# Loginator.net
KiCad netlist of a schematic drawn in EAGLE
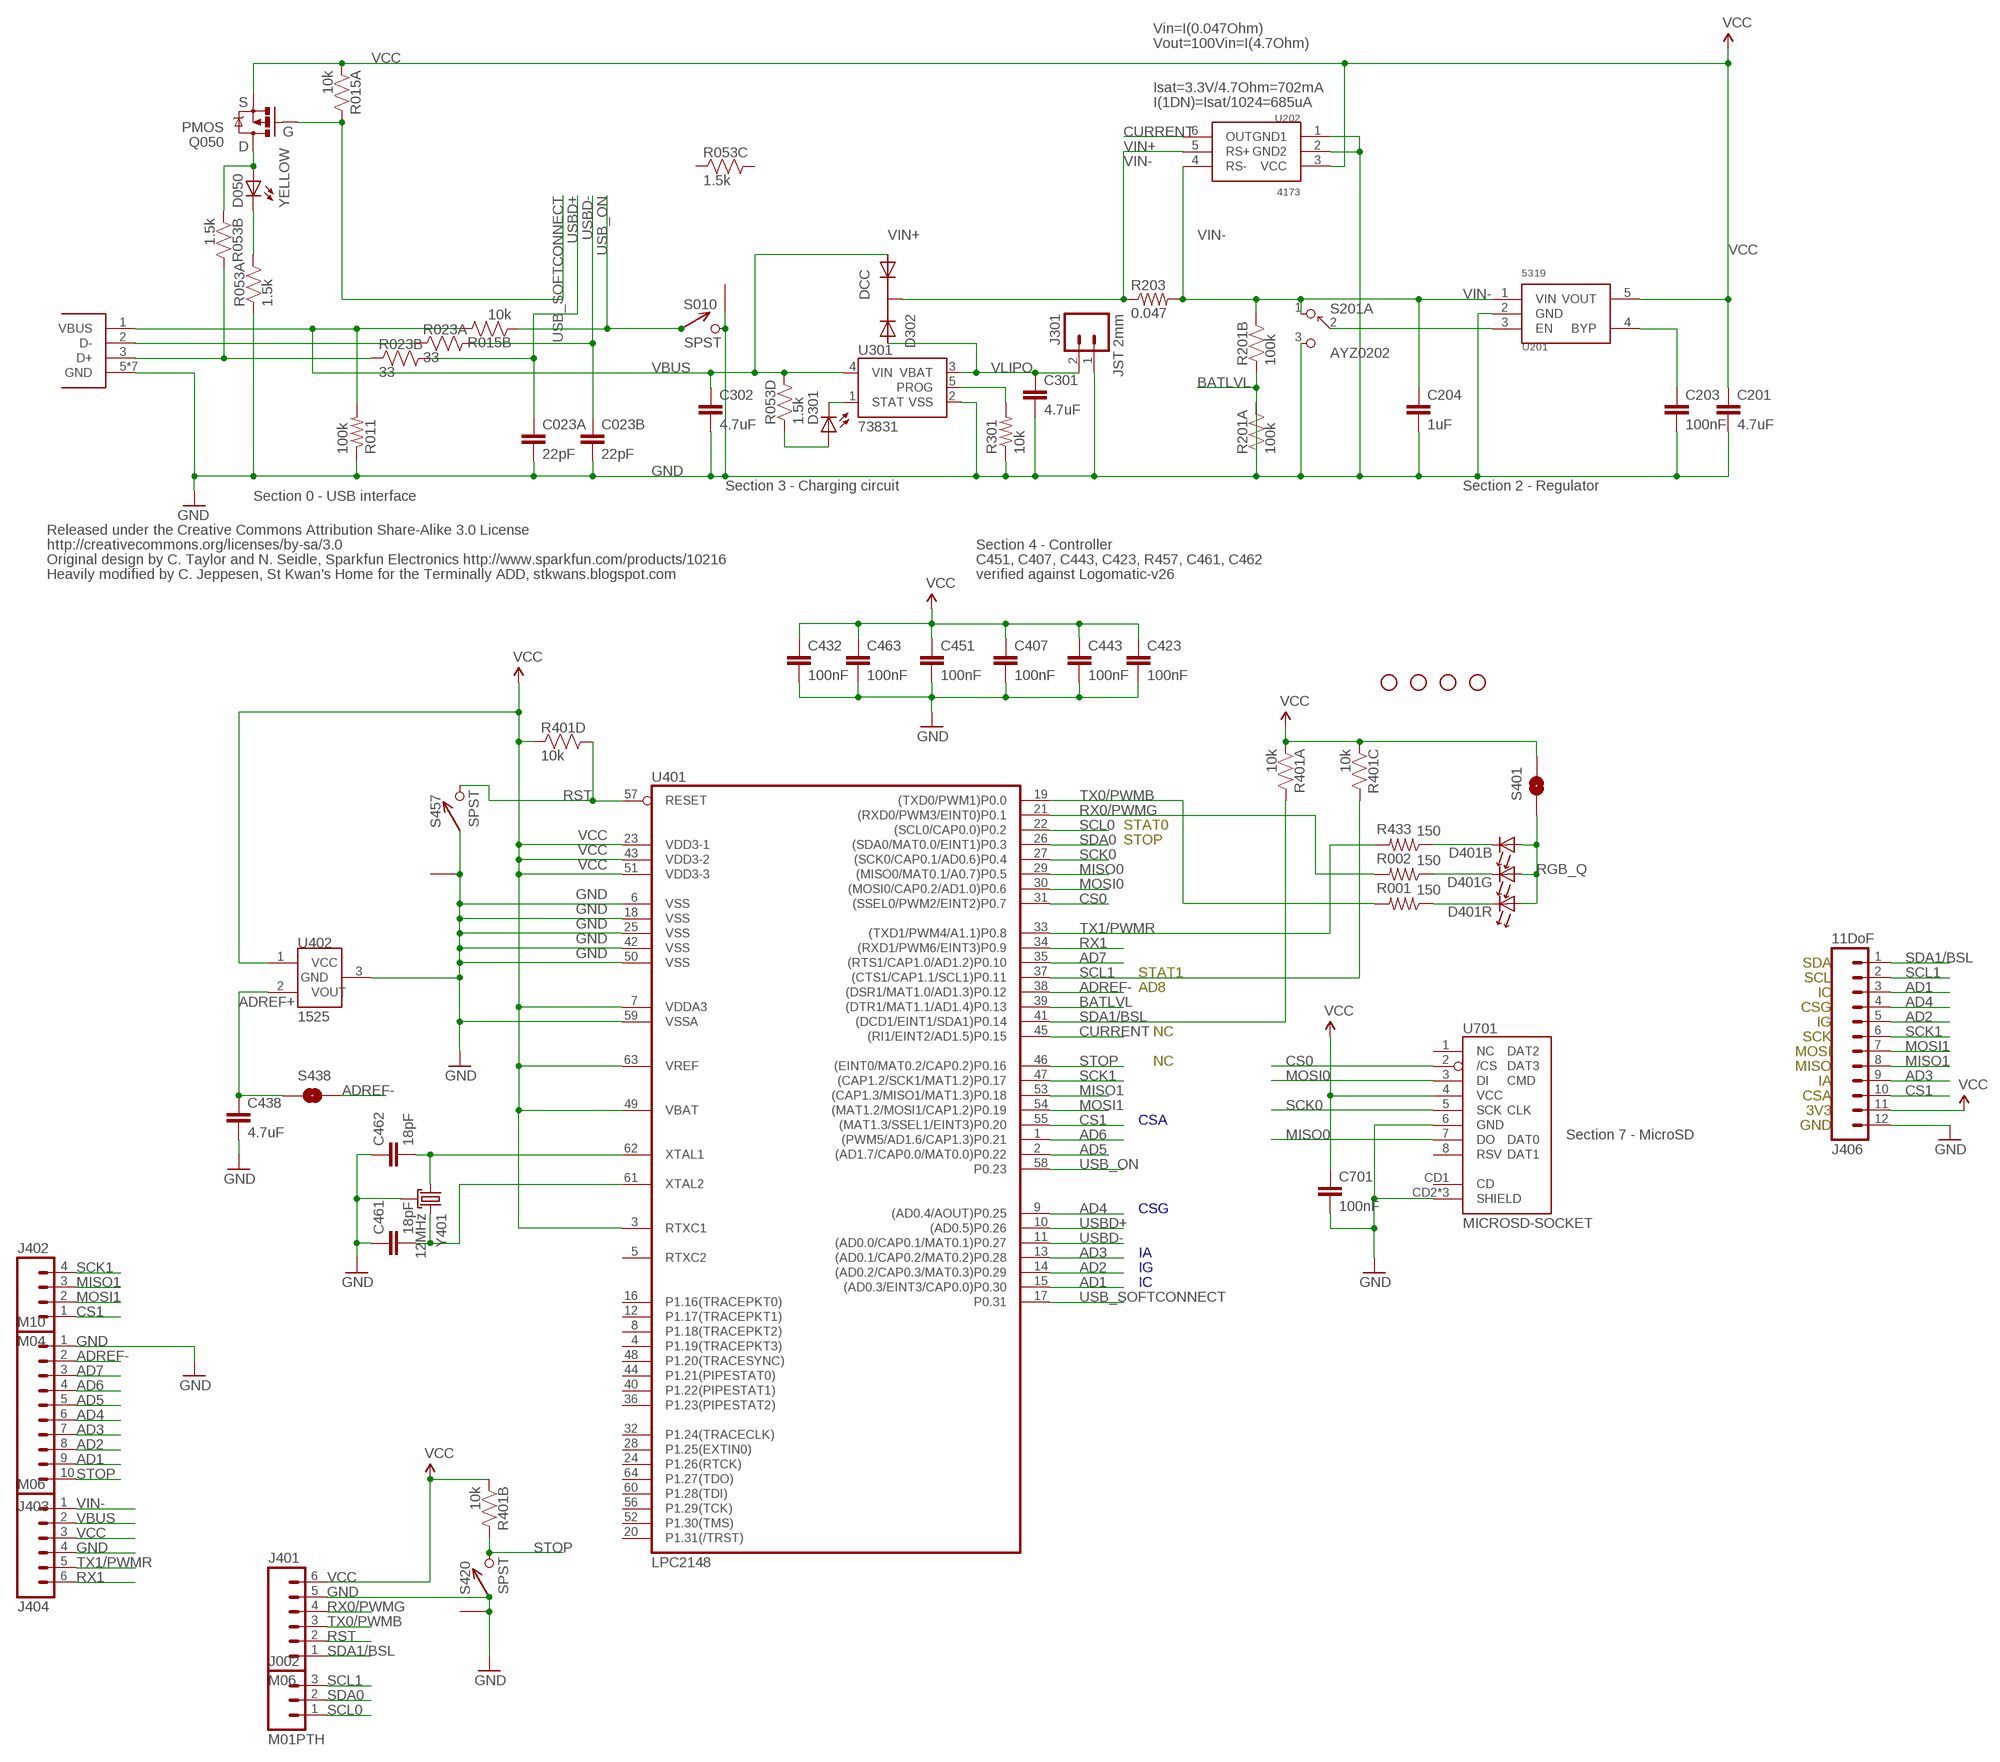
[diagram p0: schematic, sheet 1]

(export (version "E")
  (design (tool "Eeschema 10.0.6"))
  (components
    (comp (ref "C023")
      (value "22pF")
      (footprint "eagle-import:CKCM25")
      (libsource (lib "eagle-import") (part "CKCM25"))
    )
    (comp (ref "C201")
      (value "4.7uF")
      (footprint "eagle-import:0402-CAP")
      (libsource (lib "eagle-import") (part "CAP0402-CAP"))
    )
    (comp (ref "C203")
      (value "100nF")
      (footprint "eagle-import:0402-CAP")
      (libsource (lib "eagle-import") (part "CAP0402-CAP"))
    )
    (comp (ref "C204")
      (value "1uF")
      (footprint "eagle-import:0402-CAP")
      (libsource (lib "eagle-import") (part "CAP0402-CAP"))
    )
    (comp (ref "C301")
      (value "4.7uF")
      (footprint "eagle-import:0402-CAP")
      (libsource (lib "eagle-import") (part "CAP0402-CAP"))
    )
    (comp (ref "C302")
      (value "4.7uF")
      (footprint "eagle-import:0402-CAP")
      (libsource (lib "eagle-import") (part "CAP0402-CAP"))
    )
    (comp (ref "C407")
      (value "100nF")
      (footprint "eagle-import:0402-CAP")
      (libsource (lib "eagle-import") (part "CAP0402-CAP"))
    )
    (comp (ref "C423")
      (value "100nF")
      (footprint "eagle-import:0402-CAP")
      (libsource (lib "eagle-import") (part "CAP0402-CAP"))
    )
    (comp (ref "C432")
      (value "100nF")
      (footprint "eagle-import:0402-CAP")
      (libsource (lib "eagle-import") (part "CAP0402-CAP"))
    )
    (comp (ref "C438")
      (value "4.7uF")
      (footprint "eagle-import:0402-CAP")
      (libsource (lib "eagle-import") (part "CAP0402-CAP"))
    )
    (comp (ref "C443")
      (value "100nF")
      (footprint "eagle-import:0402-CAP")
      (libsource (lib "eagle-import") (part "CAP0402-CAP"))
    )
    (comp (ref "C451")
      (value "100nF")
      (footprint "eagle-import:0402-CAP")
      (libsource (lib "eagle-import") (part "CAP0402-CAP"))
    )
    (comp (ref "C461")
      (value "18pF")
      (footprint "eagle-import:0402-CAP")
      (libsource (lib "eagle-import") (part "CAP0402-CAP"))
    )
    (comp (ref "C462")
      (value "18pF")
      (footprint "eagle-import:0402-CAP")
      (libsource (lib "eagle-import") (part "CAP0402-CAP"))
    )
    (comp (ref "C463")
      (value "100nF")
      (footprint "eagle-import:0402-CAP")
      (libsource (lib "eagle-import") (part "CAP0402-CAP"))
    )
    (comp (ref "C701")
      (value "100nF")
      (footprint "eagle-import:0402-CAP")
      (libsource (lib "eagle-import") (part "CAP0402-CAP"))
    )
    (comp (ref "D050")
      (value "YELLOW")
      (footprint "eagle-import:LED-0603")
      (libsource (lib "eagle-import") (part "LED0603"))
    )
    (comp (ref "D301")
      (value "BLUE")
      (footprint "eagle-import:LED-0603")
      (libsource (lib "eagle-import") (part "LED0603"))
    )
    (comp (ref "D302")
      (value "DCC")
      (footprint "eagle-import:SOT-23-3")
      (libsource (lib "eagle-import") (part "PMEG2005CT"))
    )
    (comp (ref "D401")
      (value "SMLP36RGB2W(R)")
      (footprint "eagle-import:SMLP36")
      (libsource (lib "eagle-import") (part "SMLP36RGB2W(R)"))
    )
    (comp (ref "J001")
      (value "USB_MICROB_JSTGCT")
      (footprint "eagle-import:USB_MICROB_3075")
      (libsource (lib "eagle-import") (part "USB_MICROB_JSTGCT"))
    )
    (comp (ref "J002")
      (value "M01PTH")
      (footprint "eagle-import:1X03")
      (libsource (lib "eagle-import") (part "M03PTH"))
    )
    (comp (ref "J301")
      (value "JST 2mm")
      (footprint "eagle-import:JST-2-SMD")
      (libsource (lib "eagle-import") (part "M02-JST-2MM-SMT"))
    )
    (comp (ref "J401")
      (value "M06")
      (footprint "eagle-import:1X06")
      (libsource (lib "eagle-import") (part "M06SIP"))
    )
    (comp (ref "J402")
      (value "M04")
      (footprint "eagle-import:1X04")
      (libsource (lib "eagle-import") (part "M04PTH"))
    )
    (comp (ref "J403")
      (value "M10")
      (footprint "eagle-import:1X10")
      (libsource (lib "eagle-import") (part "M10{dblquote}"))
    )
    (comp (ref "J404")
      (value "M06")
      (footprint "eagle-import:1X06")
      (libsource (lib "eagle-import") (part "M06SIP"))
    )
    (comp (ref "J406")
      (value "11DoF")
      (footprint "eagle-import:1X12")
      (libsource (lib "eagle-import") (part "M12PTH"))
    )
    (comp (ref "JP1")
      (value "STAND-OFF")
      (footprint "eagle-import:STAND-OFF")
      (libsource (lib "eagle-import") (part "STAND-OFF"))
    )
    (comp (ref "JP2")
      (value "STAND-OFF")
      (footprint "eagle-import:STAND-OFF")
      (libsource (lib "eagle-import") (part "STAND-OFF"))
    )
    (comp (ref "JP3")
      (value "STAND-OFF")
      (footprint "eagle-import:STAND-OFF")
      (libsource (lib "eagle-import") (part "STAND-OFF"))
    )
    (comp (ref "JP4")
      (value "STAND-OFF")
      (footprint "eagle-import:STAND-OFF")
      (libsource (lib "eagle-import") (part "STAND-OFF"))
    )
    (comp (ref "Q050")
      (value "PMOS")
      (footprint "eagle-import:SOT23-3")
      (libsource (lib "eagle-import") (part "MOSFET-PCHANNELSMD"))
    )
    (comp (ref "R001")
      (value "150")
      (footprint "eagle-import:0402-RES")
      (libsource (lib "eagle-import") (part "RESISTOR0402-RES"))
    )
    (comp (ref "R002")
      (value "150")
      (footprint "eagle-import:0402-RES")
      (libsource (lib "eagle-import") (part "RESISTOR0402-RES"))
    )
    (comp (ref "R011")
      (value "100k")
      (footprint "eagle-import:0402-RES")
      (libsource (lib "eagle-import") (part "RESISTOR0402-RES"))
    )
    (comp (ref "R015")
      (value "10k")
      (footprint "eagle-import:CRA02")
      (libsource (lib "eagle-import") (part "RP2EXB24V"))
    )
    (comp (ref "R023")
      (value "33")
      (footprint "eagle-import:CRA02")
      (libsource (lib "eagle-import") (part "RP2EXB24V"))
    )
    (comp (ref "R053")
      (value "1.5k")
      (footprint "eagle-import:CRA04")
      (libsource (lib "eagle-import") (part "RP404"))
    )
    (comp (ref "R201")
      (value "100k")
      (footprint "eagle-import:CRA02")
      (libsource (lib "eagle-import") (part "RP2EXB24V"))
    )
    (comp (ref "R203")
      (value "0.047")
      (footprint "eagle-import:0402-RES")
      (libsource (lib "eagle-import") (part "RESISTOR0402-RES"))
    )
    (comp (ref "R301")
      (value "10k")
      (footprint "eagle-import:0402-RES")
      (libsource (lib "eagle-import") (part "RESISTOR0402-RES"))
    )
    (comp (ref "R401")
      (value "10k")
      (footprint "eagle-import:CRA04")
      (libsource (lib "eagle-import") (part "RP404"))
    )
    (comp (ref "R433")
      (value "150")
      (footprint "eagle-import:0402-RES")
      (libsource (lib "eagle-import") (part "RESISTOR0402-RES"))
    )
    (comp (ref "S010")
      (value "SPST")
      (footprint "eagle-import:B3U-1100P")
      (libsource (lib "eagle-import") (part "B3U-1100P"))
    )
    (comp (ref "S201")
      (value "AYZ0202")
      (footprint "eagle-import:AYZ0202")
      (libsource (lib "eagle-import") (part "AYZ0202"))
    )
    (comp (ref "S401")
      (value "SOLDERJUMPERNO")
      (footprint "eagle-import:SJ_2S-NO")
      (libsource (lib "eagle-import") (part "SOLDERJUMPERNO"))
    )
    (comp (ref "S420")
      (value "SPST")
      (footprint "eagle-import:B3U-1100P")
      (libsource (lib "eagle-import") (part "B3U-1100P"))
    )
    (comp (ref "S438")
      (value "SOLDERJUMPERNO")
      (footprint "eagle-import:SJ_2S-NO")
      (libsource (lib "eagle-import") (part "SOLDERJUMPERNO"))
    )
    (comp (ref "S457")
      (value "SPST")
      (footprint "eagle-import:B3U-1100P")
      (libsource (lib "eagle-import") (part "B3U-1100P"))
    )
    (comp (ref "U201")
      (value "5319")
      (footprint "eagle-import:SOT-23-5")
      (libsource (lib "eagle-import") (part "MIC5319D5"))
    )
    (comp (ref "U202")
      (value "4173")
      (footprint "eagle-import:SOT-23-6")
      (libsource (lib "eagle-import") (part "MAX4173"))
    )
    (comp (ref "U301")
      (value "73831")
      (footprint "eagle-import:SOT23-5")
      (libsource (lib "eagle-import") (part "MCP73831"))
    )
    (comp (ref "U401")
      (value "LPC2148")
      (footprint "eagle-import:SQFP-S-10X10-64")
      (libsource (lib "eagle-import") (part "LPC213X"))
    )
    (comp (ref "U402")
      (value "1525")
      (footprint "eagle-import:SOT-23-3")
      (libsource (lib "eagle-import") (part "MCP1525"))
    )
    (comp (ref "U701")
      (value "MICROSD-SOCKET")
      (footprint "eagle-import:MICROSD-SOCKET-PP")
      (libsource (lib "eagle-import") (part "MICROSD-SOCKET"))
    )
    (comp (ref "Y401")
      (value "12MHz")
      (footprint "eagle-import:CRYSTAL_SMD_2MM_2_5MM")
      (libsource (lib "eagle-import") (part "CX2520"))
    )
  )
  (nets
    (net (code "1") (name "/AD1") (class "Default")
      (node (ref "J403") (pin "9") (pinfunction "9_9") (pintype "passive"))
      (node (ref "J406") (pin "3") (pinfunction "3_3") (pintype "passive"))
      (node (ref "U401") (pin "15") (pinfunction "(AD0.3/EINT3/CAP0.0)P0.30_15") (pintype "bidirectional"))
    )
    (net (code "2") (name "/AD2") (class "Default")
      (node (ref "J403") (pin "8") (pinfunction "8_8") (pintype "passive"))
      (node (ref "J406") (pin "5") (pinfunction "5_5") (pintype "passive"))
      (node (ref "U401") (pin "14") (pinfunction "(AD0.2/CAP0.3/MAT0.3)P0.29_14") (pintype "bidirectional"))
    )
    (net (code "3") (name "/AD3") (class "Default")
      (node (ref "J403") (pin "7") (pinfunction "7_7") (pintype "passive"))
      (node (ref "J406") (pin "9") (pinfunction "9_9") (pintype "passive"))
      (node (ref "U401") (pin "13") (pinfunction "(AD0.1/CAP0.2/MAT0.2)P0.28_13") (pintype "bidirectional"))
    )
    (net (code "4") (name "/AD4") (class "Default")
      (node (ref "J403") (pin "6") (pinfunction "6_6") (pintype "passive"))
      (node (ref "J406") (pin "4") (pinfunction "4_4") (pintype "passive"))
      (node (ref "U401") (pin "9") (pinfunction "(AD0.4/AOUT)P0.25_9") (pintype "bidirectional"))
    )
    (net (code "5") (name "/AD5") (class "Default")
      (node (ref "J403") (pin "5") (pinfunction "5_5") (pintype "passive"))
      (node (ref "U401") (pin "2") (pinfunction "(AD1.7/CAP0.0/MAT0.0)P0.22_2") (pintype "bidirectional"))
    )
    (net (code "6") (name "/AD6") (class "Default")
      (node (ref "J403") (pin "4") (pinfunction "4_4") (pintype "passive"))
      (node (ref "U401") (pin "1") (pinfunction "(PWM5/AD1.6/CAP1.3)P0.21_1") (pintype "bidirectional"))
    )
    (net (code "7") (name "/AD7") (class "Default")
      (node (ref "J403") (pin "3") (pinfunction "3_3") (pintype "passive"))
      (node (ref "U401") (pin "35") (pinfunction "(RTS1/CAP1.0/AD1.2)P0.10_35") (pintype "bidirectional"))
    )
    (net (code "8") (name "/ADREF+") (class "Default")
      (node (ref "C438") (pin "1") (pinfunction "1_1") (pintype "passive"))
      (node (ref "S438") (pin "1") (pinfunction "1_1") (pintype "passive"))
      (node (ref "U402") (pin "2") (pinfunction "VOUT_2") (pintype "bidirectional"))
    )
    (net (code "9") (name "/ADREF-") (class "Default")
      (node (ref "J403") (pin "2") (pinfunction "2_2") (pintype "passive"))
      (node (ref "S438") (pin "2") (pinfunction "2_2") (pintype "passive"))
      (node (ref "U401") (pin "38") (pinfunction "(DSR1/MAT1.0/AD1.3)P0.12_38") (pintype "bidirectional"))
    )
    (net (code "10") (name "/BATLVL") (class "Default")
      (node (ref "R201") (pin "1") (pinfunction "1_1") (pintype "passive"))
      (node (ref "R201") (pin "2") (pinfunction "1_2") (pintype "passive"))
      (node (ref "U401") (pin "39") (pinfunction "(DTR1/MAT1.1/AD1.4)P0.13_39") (pintype "bidirectional"))
    )
    (net (code "11") (name "/CS0") (class "Default")
      (node (ref "U401") (pin "31") (pinfunction "(SSEL0/PWM2/EINT2)P0.7_31") (pintype "bidirectional"))
      (node (ref "U701") (pin "2") (pinfunction "/CS_2") (pintype "bidirectional"))
    )
    (net (code "12") (name "/CS1") (class "Default")
      (node (ref "J402") (pin "1") (pinfunction "1_1") (pintype "passive"))
      (node (ref "J406") (pin "10") (pinfunction "10_10") (pintype "passive"))
      (node (ref "U401") (pin "55") (pinfunction "(MAT1.3/SSEL1/EINT3)P0.20_55") (pintype "bidirectional"))
    )
    (net (code "13") (name "/CURRENT") (class "Default")
      (node (ref "U202") (pin "6") (pinfunction "OUT_6") (pintype "bidirectional"))
      (node (ref "U401") (pin "45") (pinfunction "(RI1/EINT2/AD1.5)P0.15_45") (pintype "bidirectional"))
    )
    (net (code "14") (name "/MISO0") (class "Default")
      (node (ref "U401") (pin "29") (pinfunction "(MISO0/MAT0.1/A0.7)P0.5_29") (pintype "bidirectional"))
      (node (ref "U701") (pin "7") (pinfunction "DO_7") (pintype "bidirectional"))
    )
    (net (code "15") (name "/MISO1") (class "Default")
      (node (ref "J402") (pin "3") (pinfunction "3_3") (pintype "passive"))
      (node (ref "J406") (pin "8") (pinfunction "8_8") (pintype "passive"))
      (node (ref "U401") (pin "53") (pinfunction "(CAP1.3/MISO1/MAT1.3)P0.18_53") (pintype "bidirectional"))
    )
    (net (code "16") (name "/MOSI0") (class "Default")
      (node (ref "U401") (pin "30") (pinfunction "(MOSI0/CAP0.2/AD1.0)P0.6_30") (pintype "bidirectional"))
      (node (ref "U701") (pin "3") (pinfunction "DI_3") (pintype "bidirectional"))
    )
    (net (code "17") (name "/MOSI1") (class "Default")
      (node (ref "J402") (pin "2") (pinfunction "2_2") (pintype "passive"))
      (node (ref "J406") (pin "7") (pinfunction "7_7") (pintype "passive"))
      (node (ref "U401") (pin "54") (pinfunction "(MAT1.2/MOSI1/CAP1.2)P0.19_54") (pintype "bidirectional"))
    )
    (net (code "18") (name "/RGB_Q") (class "Default")
      (node (ref "D401") (pin "2") (pinfunction "A_2") (pintype "passive"))
      (node (ref "D401") (pin "4") (pinfunction "A_4") (pintype "passive"))
      (node (ref "D401") (pin "6") (pinfunction "A_6") (pintype "passive"))
      (node (ref "S401") (pin "1") (pinfunction "1_1") (pintype "passive"))
    )
    (net (code "19") (name "/RST") (class "Default")
      (node (ref "J401") (pin "2") (pinfunction "2_2") (pintype "passive"))
      (node (ref "R401") (pin "5") (pinfunction "2_5") (pintype "passive"))
      (node (ref "S457") (pin "P$2") (pinfunction "2_P$2") (pintype "bidirectional"))
      (node (ref "U401") (pin "57") (pinfunction "RESET_57") (pintype "input"))
    )
    (net (code "20") (name "/RX0{slash}PWMG") (class "Default")
      (node (ref "J401") (pin "4") (pinfunction "4_4") (pintype "passive"))
      (node (ref "R002") (pin "2") (pinfunction "2_2") (pintype "passive"))
      (node (ref "U401") (pin "21") (pinfunction "(RXD0/PWM3/EINT0)P0.1_21") (pintype "bidirectional"))
    )
    (net (code "21") (name "/RX1") (class "Default")
      (node (ref "J404") (pin "6") (pinfunction "6_6") (pintype "passive"))
      (node (ref "U401") (pin "34") (pinfunction "(RXD1/PWM6/EINT3)P0.9_34") (pintype "bidirectional"))
    )
    (net (code "22") (name "/SCK0") (class "Default")
      (node (ref "U401") (pin "27") (pinfunction "(SCK0/CAP0.1/AD0.6)P0.4_27") (pintype "bidirectional"))
      (node (ref "U701") (pin "5") (pinfunction "SCK_5") (pintype "bidirectional"))
    )
    (net (code "23") (name "/SCK1") (class "Default")
      (node (ref "J402") (pin "4") (pinfunction "4_4") (pintype "passive"))
      (node (ref "J406") (pin "6") (pinfunction "6_6") (pintype "passive"))
      (node (ref "U401") (pin "47") (pinfunction "(CAP1.2/SCK1/MAT1.2)P0.17_47") (pintype "bidirectional"))
    )
    (net (code "24") (name "/SCL0") (class "Default")
      (node (ref "J002") (pin "1") (pinfunction "1_1") (pintype "passive"))
      (node (ref "U401") (pin "22") (pinfunction "(SCL0/CAP0.0)P0.2_22") (pintype "bidirectional"))
    )
    (net (code "25") (name "/SCL1") (class "Default")
      (node (ref "J002") (pin "3") (pinfunction "3_3") (pintype "passive"))
      (node (ref "J406") (pin "2") (pinfunction "2_2") (pintype "passive"))
      (node (ref "R401") (pin "6") (pinfunction "2_6") (pintype "passive"))
      (node (ref "U401") (pin "37") (pinfunction "(CTS1/CAP1.1/SCL1)P0.11_37") (pintype "bidirectional"))
    )
    (net (code "26") (name "/SDA0") (class "Default")
      (node (ref "J002") (pin "2") (pinfunction "2_2") (pintype "passive"))
      (node (ref "U401") (pin "26") (pinfunction "(SDA0/MAT0.0/EINT1)P0.3_26") (pintype "bidirectional"))
    )
    (net (code "27") (name "/SDA1{slash}BSL") (class "Default")
      (node (ref "J401") (pin "1") (pinfunction "1_1") (pintype "passive"))
      (node (ref "J406") (pin "1") (pinfunction "1_1") (pintype "passive"))
      (node (ref "R401") (pin "8") (pinfunction "2_8") (pintype "passive"))
      (node (ref "U401") (pin "41") (pinfunction "(DCD1/EINT1/SDA1)P0.14_41") (pintype "bidirectional"))
    )
    (net (code "28") (name "/STOP") (class "Default")
      (node (ref "J403") (pin "10") (pinfunction "10_10") (pintype "passive"))
      (node (ref "R401") (pin "7") (pinfunction "2_7") (pintype "passive"))
      (node (ref "S420") (pin "P$2") (pinfunction "2_P$2") (pintype "bidirectional"))
      (node (ref "U401") (pin "46") (pinfunction "(EINT0/MAT0.2/CAP0.2)P0.16_46") (pintype "bidirectional"))
    )
    (net (code "29") (name "/TX0{slash}PWMB") (class "Default")
      (node (ref "J401") (pin "3") (pinfunction "3_3") (pintype "passive"))
      (node (ref "R001") (pin "2") (pinfunction "2_2") (pintype "passive"))
      (node (ref "U401") (pin "19") (pinfunction "(TXD0/PWM1)P0.0_19") (pintype "bidirectional"))
    )
    (net (code "30") (name "/TX1{slash}PWMR") (class "Default")
      (node (ref "J404") (pin "5") (pinfunction "5_5") (pintype "passive"))
      (node (ref "R433") (pin "2") (pinfunction "2_2") (pintype "passive"))
      (node (ref "U401") (pin "33") (pinfunction "(TXD1/PWM4/A1.1)P0.8_33") (pintype "bidirectional"))
    )
    (net (code "31") (name "/USBD+") (class "Default")
      (node (ref "C023") (pin "1") (pinfunction "1_1") (pintype "passive"))
      (node (ref "R023") (pin "3") (pinfunction "2_3") (pintype "passive"))
      (node (ref "U401") (pin "10") (pinfunction "(AD0.5)P0.26_10") (pintype "bidirectional"))
    )
    (net (code "32") (name "/USBD-") (class "Default")
      (node (ref "C023") (pin "2") (pinfunction "1_2") (pintype "passive"))
      (node (ref "R023") (pin "4") (pinfunction "2_4") (pintype "passive"))
      (node (ref "U401") (pin "11") (pinfunction "(AD0.0/CAP0.1/MAT0.1)P0.27_11") (pintype "bidirectional"))
    )
    (net (code "33") (name "/USB_ON") (class "Default")
      (node (ref "R015") (pin "2") (pinfunction "1_2") (pintype "passive"))
      (node (ref "S010") (pin "P$1") (pinfunction "1_P$1") (pintype "bidirectional"))
      (node (ref "U401") (pin "58") (pinfunction "P0.23_58") (pintype "bidirectional"))
    )
    (net (code "34") (name "/USB_SOFTCONNECT") (class "Default")
      (node (ref "Q050") (pin "1") (pinfunction "G_1") (pintype "passive"))
      (node (ref "R015") (pin "4") (pinfunction "2_4") (pintype "passive"))
      (node (ref "U401") (pin "17") (pinfunction "P0.31_17") (pintype "output"))
    )
    (net (code "35") (name "/VBUS") (class "Default")
      (node (ref "C302") (pin "1") (pinfunction "1_1") (pintype "passive"))
      (node (ref "D302") (pin "1") (pinfunction "A1_1") (pintype "passive"))
      (node (ref "J001") (pin "1") (pinfunction "VBUS_1") (pintype "bidirectional"))
      (node (ref "J404") (pin "2") (pinfunction "2_2") (pintype "passive"))
      (node (ref "R011") (pin "2") (pinfunction "2_2") (pintype "passive"))
      (node (ref "R015") (pin "3") (pinfunction "2_3") (pintype "passive"))
      (node (ref "R053") (pin "5") (pinfunction "2_5") (pintype "passive"))
      (node (ref "U301") (pin "4") (pinfunction "VIN_4") (pintype "power_in"))
    )
    (net (code "36") (name "/VIN+") (class "Default")
      (node (ref "D302") (pin "3") (pinfunction "K_3") (pintype "passive"))
      (node (ref "R203") (pin "1") (pinfunction "1_1") (pintype "passive"))
      (node (ref "U202") (pin "5") (pinfunction "RS+_5") (pintype "bidirectional"))
    )
    (net (code "37") (name "/VIN-") (class "Default")
      (node (ref "C204") (pin "1") (pinfunction "1_1") (pintype "passive"))
      (node (ref "J404") (pin "1") (pinfunction "1_1") (pintype "passive"))
      (node (ref "R201") (pin "3") (pinfunction "2_3") (pintype "passive"))
      (node (ref "R203") (pin "2") (pinfunction "2_2") (pintype "passive"))
      (node (ref "S201") (pin "1") (pinfunction "P$1_1") (pintype "bidirectional"))
      (node (ref "U201") (pin "1") (pinfunction "VIN_1") (pintype "bidirectional"))
      (node (ref "U202") (pin "4") (pinfunction "RS-_4") (pintype "bidirectional"))
    )
    (net (code "38") (name "/VLIPO") (class "Default")
      (node (ref "C301") (pin "1") (pinfunction "1_1") (pintype "passive"))
      (node (ref "D302") (pin "2") (pinfunction "A2_2") (pintype "passive"))
      (node (ref "J301") (pin "2") (pinfunction "2_2") (pintype "passive"))
      (node (ref "U301") (pin "3") (pinfunction "VBAT_3") (pintype "power_in"))
    )
    (net (code "39") (name "GND") (class "Default")
      (node (ref "C023") (pin "3") (pinfunction "2_3") (pintype "passive"))
      (node (ref "C023") (pin "4") (pinfunction "2_4") (pintype "passive"))
      (node (ref "C201") (pin "2") (pinfunction "2_2") (pintype "passive"))
      (node (ref "C203") (pin "2") (pinfunction "2_2") (pintype "passive"))
      (node (ref "C204") (pin "2") (pinfunction "2_2") (pintype "passive"))
      (node (ref "C301") (pin "2") (pinfunction "2_2") (pintype "passive"))
      (node (ref "C302") (pin "2") (pinfunction "2_2") (pintype "passive"))
      (node (ref "C407") (pin "2") (pinfunction "2_2") (pintype "passive"))
      (node (ref "C423") (pin "2") (pinfunction "2_2") (pintype "passive"))
      (node (ref "C432") (pin "2") (pinfunction "2_2") (pintype "passive"))
      (node (ref "C438") (pin "2") (pinfunction "2_2") (pintype "passive"))
      (node (ref "C443") (pin "2") (pinfunction "2_2") (pintype "passive"))
      (node (ref "C451") (pin "2") (pinfunction "2_2") (pintype "passive"))
      (node (ref "C461") (pin "1") (pinfunction "1_1") (pintype "passive"))
      (node (ref "C462") (pin "1") (pinfunction "1_1") (pintype "passive"))
      (node (ref "C463") (pin "2") (pinfunction "2_2") (pintype "passive"))
      (node (ref "C701") (pin "2") (pinfunction "2_2") (pintype "passive"))
      (node (ref "J001") (pin "5") (pinfunction "GND_5") (pintype "bidirectional"))
      (node (ref "J001") (pin "P$1") (pinfunction "GND_P$1") (pintype "bidirectional"))
      (node (ref "J001") (pin "P$10") (pinfunction "GND_P$10") (pintype "bidirectional"))
      (node (ref "J001") (pin "P$2") (pinfunction "GND_P$2") (pintype "bidirectional"))
      (node (ref "J001") (pin "P$3") (pinfunction "GND_P$3") (pintype "bidirectional"))
      (node (ref "J001") (pin "P$4") (pinfunction "GND_P$4") (pintype "bidirectional"))
      (node (ref "J001") (pin "P$8") (pinfunction "GND_P$8") (pintype "bidirectional"))
      (node (ref "J301") (pin "1") (pinfunction "1_1") (pintype "passive"))
      (node (ref "J401") (pin "5") (pinfunction "5_5") (pintype "passive"))
      (node (ref "J403") (pin "1") (pinfunction "1_1") (pintype "passive"))
      (node (ref "J404") (pin "4") (pinfunction "4_4") (pintype "passive"))
      (node (ref "J406") (pin "12") (pinfunction "12_12") (pintype "passive"))
      (node (ref "R011") (pin "1") (pinfunction "1_1") (pintype "passive"))
      (node (ref "R053") (pin "1") (pinfunction "1_1") (pintype "passive"))
      (node (ref "R201") (pin "4") (pinfunction "2_4") (pintype "passive"))
      (node (ref "R301") (pin "1") (pinfunction "1_1") (pintype "passive"))
      (node (ref "S010") (pin "P$2") (pinfunction "2_P$2") (pintype "bidirectional"))
      (node (ref "S010") (pin "P$3") (pinfunction "1_P$3") (pintype "bidirectional"))
      (node (ref "S201") (pin "3") (pinfunction "P$2_3") (pintype "bidirectional"))
      (node (ref "S420") (pin "P$1") (pinfunction "1_P$1") (pintype "bidirectional"))
      (node (ref "S420") (pin "P$3") (pinfunction "1_P$3") (pintype "bidirectional"))
      (node (ref "S457") (pin "P$1") (pinfunction "1_P$1") (pintype "bidirectional"))
      (node (ref "S457") (pin "P$3") (pinfunction "1_P$3") (pintype "bidirectional"))
      (node (ref "U201") (pin "2") (pinfunction "GND_2") (pintype "bidirectional"))
      (node (ref "U202") (pin "1") (pinfunction "GND1_1") (pintype "bidirectional"))
      (node (ref "U202") (pin "2") (pinfunction "GND2_2") (pintype "bidirectional"))
      (node (ref "U301") (pin "2") (pinfunction "VSS_2") (pintype "power_in"))
      (node (ref "U401") (pin "18") (pinfunction "VSS_18") (pintype "power_in"))
      (node (ref "U401") (pin "25") (pinfunction "VSS_25") (pintype "power_in"))
      (node (ref "U401") (pin "42") (pinfunction "VSS_42") (pintype "power_in"))
      (node (ref "U401") (pin "50") (pinfunction "VSS_50") (pintype "power_in"))
      (node (ref "U401") (pin "59") (pinfunction "VSSA_59") (pintype "power_in"))
      (node (ref "U401") (pin "6") (pinfunction "VSS_6") (pintype "power_in"))
      (node (ref "U402") (pin "3") (pinfunction "GND_3") (pintype "bidirectional"))
      (node (ref "U701") (pin "6") (pinfunction "GND_6") (pintype "bidirectional"))
      (node (ref "U701") (pin "CD2") (pinfunction "SHIELD_CD2") (pintype "bidirectional"))
      (node (ref "U701") (pin "GND1") (pinfunction "SHIELD_GND1") (pintype "bidirectional"))
      (node (ref "U701") (pin "GND3") (pinfunction "SHIELD_GND3") (pintype "bidirectional"))
      (node (ref "Y401") (pin "2") (pinfunction "P$1_2") (pintype "passive"))
      (node (ref "Y401") (pin "4") (pinfunction "P$1_4") (pintype "passive"))
    )
    (net (code "40") (name "Net-(D401A-C)") (class "Default")
      (node (ref "D401") (pin "1") (pinfunction "C_1") (pintype "passive"))
      (node (ref "R433") (pin "1") (pinfunction "1_1") (pintype "passive"))
    )
    (net (code "41") (name "Net-(D401B-C)") (class "Default")
      (node (ref "D401") (pin "3") (pinfunction "C_3") (pintype "passive"))
      (node (ref "R002") (pin "1") (pinfunction "1_1") (pintype "passive"))
    )
    (net (code "42") (name "Net-(D401C-C)") (class "Default")
      (node (ref "D401") (pin "5") (pinfunction "C_5") (pintype "passive"))
      (node (ref "R001") (pin "1") (pinfunction "1_1") (pintype "passive"))
    )
    (net (code "43") (name "Net-(J001-D+)") (class "Default")
      (node (ref "J001") (pin "3") (pinfunction "D+_3") (pintype "bidirectional"))
      (node (ref "R023") (pin "2") (pinfunction "1_2") (pintype "passive"))
      (node (ref "R053") (pin "7") (pinfunction "2_7") (pintype "passive"))
    )
    (net (code "44") (name "Net-(J001-D-)") (class "Default")
      (node (ref "J001") (pin "2") (pinfunction "D-_2") (pintype "bidirectional"))
      (node (ref "R023") (pin "1") (pinfunction "1_1") (pintype "passive"))
    )
    (net (code "45") (name "Net-(Q050-D)") (class "Default")
      (node (ref "D050") (pin "A") (pinfunction "A_A") (pintype "passive"))
      (node (ref "Q050") (pin "3") (pinfunction "D_3") (pintype "passive"))
      (node (ref "R053") (pin "2") (pinfunction "1_2") (pintype "passive"))
    )
    (net (code "46") (name "Net-(R053A-2)") (class "Default")
      (node (ref "D050") (pin "C") (pinfunction "C_C") (pintype "passive"))
      (node (ref "R053") (pin "8") (pinfunction "2_8") (pintype "passive"))
    )
    (net (code "47") (name "Net-(R053D-1)") (class "Default")
      (node (ref "D301") (pin "A") (pinfunction "A_A") (pintype "passive"))
      (node (ref "R053") (pin "4") (pinfunction "1_4") (pintype "passive"))
    )
    (net (code "48") (name "Net-(S201A-P$3)") (class "Default")
      (node (ref "S201") (pin "2") (pinfunction "P$3_2") (pintype "bidirectional"))
      (node (ref "U201") (pin "3") (pinfunction "EN_3") (pintype "bidirectional"))
    )
    (net (code "49") (name "Net-(U201-BYP)") (class "Default")
      (node (ref "C203") (pin "1") (pinfunction "1_1") (pintype "passive"))
      (node (ref "U201") (pin "4") (pinfunction "BYP_4") (pintype "bidirectional"))
    )
    (net (code "50") (name "Net-(U301-PROG)") (class "Default")
      (node (ref "R301") (pin "2") (pinfunction "2_2") (pintype "passive"))
      (node (ref "U301") (pin "5") (pinfunction "PROG_5") (pintype "input"))
    )
    (net (code "51") (name "Net-(U301-STAT)") (class "Default")
      (node (ref "D301") (pin "C") (pinfunction "C_C") (pintype "passive"))
      (node (ref "U301") (pin "1") (pinfunction "STAT_1") (pintype "output"))
    )
    (net (code "52") (name "Net-(U401-XTAL1)") (class "Default")
      (node (ref "C462") (pin "2") (pinfunction "2_2") (pintype "passive"))
      (node (ref "U401") (pin "62") (pinfunction "XTAL1_62") (pintype "input"))
      (node (ref "Y401") (pin "1") (pinfunction "1_1") (pintype "passive"))
    )
    (net (code "53") (name "Net-(U401-XTAL2)") (class "Default")
      (node (ref "C461") (pin "2") (pinfunction "2_2") (pintype "passive"))
      (node (ref "U401") (pin "61") (pinfunction "XTAL2_61") (pintype "output"))
      (node (ref "Y401") (pin "3") (pinfunction "2_3") (pintype "passive"))
    )
    (net (code "54") (name "VCC") (class "Default")
      (node (ref "C201") (pin "1") (pinfunction "1_1") (pintype "passive"))
      (node (ref "C407") (pin "1") (pinfunction "1_1") (pintype "passive"))
      (node (ref "C423") (pin "1") (pinfunction "1_1") (pintype "passive"))
      (node (ref "C432") (pin "1") (pinfunction "1_1") (pintype "passive"))
      (node (ref "C443") (pin "1") (pinfunction "1_1") (pintype "passive"))
      (node (ref "C451") (pin "1") (pinfunction "1_1") (pintype "passive"))
      (node (ref "C463") (pin "1") (pinfunction "1_1") (pintype "passive"))
      (node (ref "C701") (pin "1") (pinfunction "1_1") (pintype "passive"))
      (node (ref "J401") (pin "6") (pinfunction "6_6") (pintype "passive"))
      (node (ref "J404") (pin "3") (pinfunction "3_3") (pintype "passive"))
      (node (ref "J406") (pin "11") (pinfunction "11_11") (pintype "passive"))
      (node (ref "Q050") (pin "2") (pinfunction "S_2") (pintype "passive"))
      (node (ref "R015") (pin "1") (pinfunction "1_1") (pintype "passive"))
      (node (ref "R401") (pin "1") (pinfunction "1_1") (pintype "passive"))
      (node (ref "R401") (pin "2") (pinfunction "1_2") (pintype "passive"))
      (node (ref "R401") (pin "3") (pinfunction "1_3") (pintype "passive"))
      (node (ref "R401") (pin "4") (pinfunction "1_4") (pintype "passive"))
      (node (ref "S401") (pin "2") (pinfunction "2_2") (pintype "passive"))
      (node (ref "U201") (pin "5") (pinfunction "VOUT_5") (pintype "bidirectional"))
      (node (ref "U202") (pin "3") (pinfunction "VCC_3") (pintype "bidirectional"))
      (node (ref "U401") (pin "23") (pinfunction "VDD3-1_23") (pintype "power_in"))
      (node (ref "U401") (pin "3") (pinfunction "RTXC1_3") (pintype "input"))
      (node (ref "U401") (pin "43") (pinfunction "VDD3-2_43") (pintype "power_in"))
      (node (ref "U401") (pin "49") (pinfunction "VBAT_49") (pintype "power_in"))
      (node (ref "U401") (pin "51") (pinfunction "VDD3-3_51") (pintype "power_in"))
      (node (ref "U401") (pin "63") (pinfunction "VREF_63") (pintype "input"))
      (node (ref "U401") (pin "7") (pinfunction "VDDA3_7") (pintype "power_in"))
      (node (ref "U402") (pin "1") (pinfunction "VCC_1") (pintype "bidirectional"))
      (node (ref "U701") (pin "4") (pinfunction "VCC_4") (pintype "bidirectional"))
    )
    (net (code "55") (name "unconnected-(R053C-1-Pad3)") (class "Default")
      (node (ref "R053") (pin "3") (pinfunction "1_3") (pintype "passive"))
    )
    (net (code "56") (name "unconnected-(R053C-2-Pad6)") (class "Default")
      (node (ref "R053") (pin "6") (pinfunction "2_6") (pintype "passive"))
    )
    (net (code "57") (name "unconnected-(U401-P1.16(TRACEPKT0)-Pad16)") (class "Default")
      (node (ref "U401") (pin "16") (pinfunction "P1.16(TRACEPKT0)_16") (pintype "bidirectional"))
    )
    (net (code "58") (name "unconnected-(U401-P1.17(TRACEPKT1)-Pad12)") (class "Default")
      (node (ref "U401") (pin "12") (pinfunction "P1.17(TRACEPKT1)_12") (pintype "bidirectional"))
    )
    (net (code "59") (name "unconnected-(U401-P1.18(TRACEPKT2)-Pad8)") (class "Default")
      (node (ref "U401") (pin "8") (pinfunction "P1.18(TRACEPKT2)_8") (pintype "bidirectional"))
    )
    (net (code "60") (name "unconnected-(U401-P1.19(TRACEPKT3)-Pad4)") (class "Default")
      (node (ref "U401") (pin "4") (pinfunction "P1.19(TRACEPKT3)_4") (pintype "bidirectional"))
    )
    (net (code "61") (name "unconnected-(U401-P1.20(TRACESYNC)-Pad48)") (class "Default")
      (node (ref "U401") (pin "48") (pinfunction "P1.20(TRACESYNC)_48") (pintype "bidirectional"))
    )
    (net (code "62") (name "unconnected-(U401-P1.21(PIPESTAT0)-Pad44)") (class "Default")
      (node (ref "U401") (pin "44") (pinfunction "P1.21(PIPESTAT0)_44") (pintype "bidirectional"))
    )
    (net (code "63") (name "unconnected-(U401-P1.22(PIPESTAT1)-Pad40)") (class "Default")
      (node (ref "U401") (pin "40") (pinfunction "P1.22(PIPESTAT1)_40") (pintype "bidirectional"))
    )
    (net (code "64") (name "unconnected-(U401-P1.23(PIPESTAT2)-Pad36)") (class "Default")
      (node (ref "U401") (pin "36") (pinfunction "P1.23(PIPESTAT2)_36") (pintype "bidirectional"))
    )
    (net (code "65") (name "unconnected-(U401-P1.24(TRACECLK)-Pad32)") (class "Default")
      (node (ref "U401") (pin "32") (pinfunction "P1.24(TRACECLK)_32") (pintype "bidirectional"))
    )
    (net (code "66") (name "unconnected-(U401-P1.25(EXTIN0)-Pad28)") (class "Default")
      (node (ref "U401") (pin "28") (pinfunction "P1.25(EXTIN0)_28") (pintype "bidirectional"))
    )
    (net (code "67") (name "unconnected-(U401-P1.26(RTCK)-Pad24)") (class "Default")
      (node (ref "U401") (pin "24") (pinfunction "P1.26(RTCK)_24") (pintype "bidirectional"))
    )
    (net (code "68") (name "unconnected-(U401-P1.27(TDO)-Pad64)") (class "Default")
      (node (ref "U401") (pin "64") (pinfunction "P1.27(TDO)_64") (pintype "bidirectional"))
    )
    (net (code "69") (name "unconnected-(U401-P1.28(TDI)-Pad60)") (class "Default")
      (node (ref "U401") (pin "60") (pinfunction "P1.28(TDI)_60") (pintype "bidirectional"))
    )
    (net (code "70") (name "unconnected-(U401-P1.29(TCK)-Pad56)") (class "Default")
      (node (ref "U401") (pin "56") (pinfunction "P1.29(TCK)_56") (pintype "bidirectional"))
    )
    (net (code "71") (name "unconnected-(U401-P1.30(TMS)-Pad52)") (class "Default")
      (node (ref "U401") (pin "52") (pinfunction "P1.30(TMS)_52") (pintype "bidirectional"))
    )
    (net (code "72") (name "unconnected-(U401-P1.31({slash}TRST)-Pad20)") (class "Default")
      (node (ref "U401") (pin "20") (pinfunction "P1.31(/TRST)_20") (pintype "bidirectional"))
    )
    (net (code "73") (name "unconnected-(U401-RTXC2-Pad5)") (class "Default")
      (node (ref "U401") (pin "5") (pinfunction "RTXC2_5") (pintype "output"))
    )
    (net (code "74") (name "unconnected-(U701-CD-PadCD1)") (class "Default")
      (node (ref "U701") (pin "CD1") (pinfunction "CD_CD1") (pintype "bidirectional"))
    )
    (net (code "75") (name "unconnected-(U701-NC-Pad1)") (class "Default")
      (node (ref "U701") (pin "1") (pinfunction "NC_1") (pintype "bidirectional"))
    )
    (net (code "76") (name "unconnected-(U701-RSV-Pad8)") (class "Default")
      (node (ref "U701") (pin "8") (pinfunction "RSV_8") (pintype "bidirectional"))
    )
  )
)
